# power.net
KiCad netlist of a schematic drawn in Altium Designer
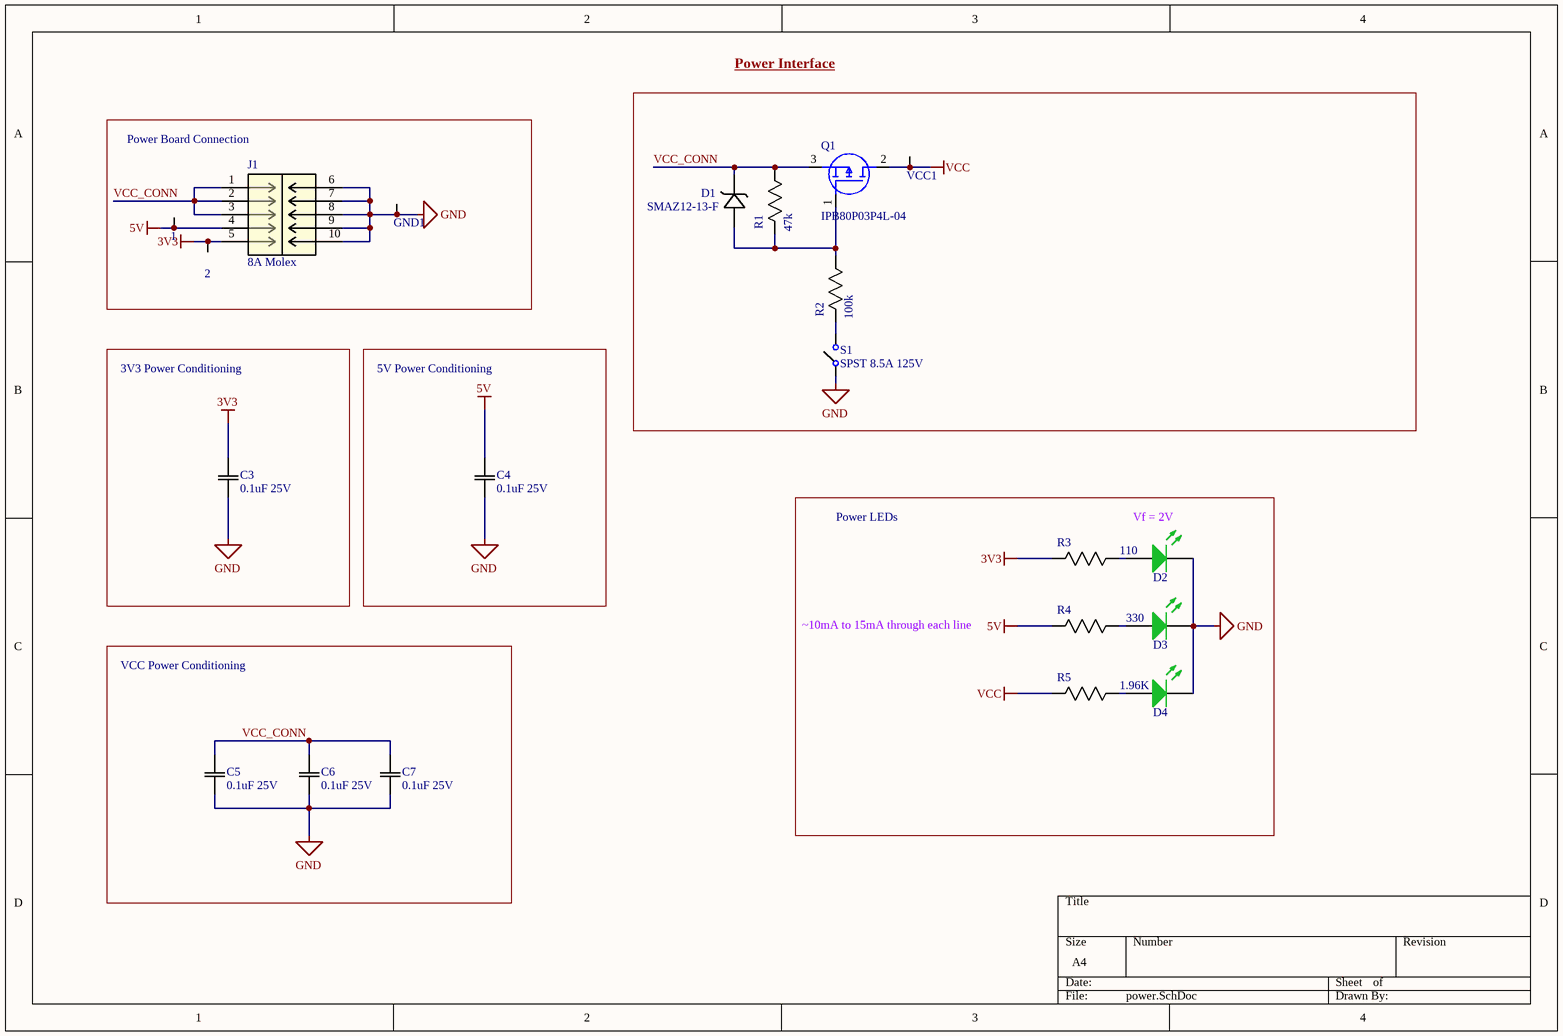
[diagram p0: power.SchDoc]

(export (version "E")
  (design (tool "Eeschema 10.0.6"))
  (components
    (comp (ref "1")
      (value "Test Point (Via)")
      (footprint "TP")
      (libsource (lib "AltiumLibraries") (part "Test Point (Via)"))
    )
    (comp (ref "2")
      (value "Test Point (Via)")
      (footprint "TP")
      (libsource (lib "AltiumLibraries") (part "Test Point (Via)"))
    )
    (comp (ref "C3")
      (value "0.1uF 25V")
      (footprint "0805")
      (description "CAP CER 0.1UF 25V X7R 0805/0603")
      (fields (field (name "TOLERANCE") "10%"))
      (libsource (lib "AltiumLibraries") (part "CAP 0.1uF 25V"))
    )
    (comp (ref "C4")
      (value "0.1uF 25V")
      (footprint "0805")
      (description "CAP CER 0.1UF 25V X7R 0805/0603")
      (fields (field (name "TOLERANCE") "10%"))
      (libsource (lib "AltiumLibraries") (part "CAP 0.1uF 25V"))
    )
    (comp (ref "C5")
      (value "0.1uF 25V")
      (footprint "0805")
      (description "CAP CER 0.1UF 25V X7R 0805/0603")
      (fields (field (name "TOLERANCE") "10%"))
      (libsource (lib "AltiumLibraries") (part "CAP 0.1uF 25V"))
    )
    (comp (ref "C6")
      (value "0.1uF 25V")
      (footprint "0805")
      (description "CAP CER 0.1UF 25V X7R 0805/0603")
      (fields (field (name "TOLERANCE") "10%"))
      (libsource (lib "AltiumLibraries") (part "CAP 0.1uF 25V"))
    )
    (comp (ref "C7")
      (value "0.1uF 25V")
      (footprint "0805")
      (description "CAP CER 0.1UF 25V X7R 0805/0603")
      (fields (field (name "TOLERANCE") "10%"))
      (libsource (lib "AltiumLibraries") (part "CAP 0.1uF 25V"))
    )
    (comp (ref "D1")
      (value "SMAZ12-13-F")
      (footprint "SMA_DIO-L")
      (description "Zener Diode 12 V 1 W ±5% Surface Mount SMA")
      (fields (field (name "COPYRIGHT") "Copyright (C) 2021 Ultra Librarian. All rights reserved."))
      (libsource (lib "AltiumLibraries") (part "DIODE ZENER 12V 1W"))
    )
    (comp (ref "D2")
      (value "LED2")
      (footprint "3.2X1.6X1.1")
      (description "Typical RED, GREEN, YELLOW, AMBER GaAs LED")
      (libsource (lib "AltiumLibraries") (part "LED GREEN SMD"))
    )
    (comp (ref "D3")
      (value "LED2")
      (footprint "3.2X1.6X1.1")
      (description "Typical RED, GREEN, YELLOW, AMBER GaAs LED")
      (libsource (lib "AltiumLibraries") (part "LED GREEN SMD"))
    )
    (comp (ref "D4")
      (value "LED2")
      (footprint "3.2X1.6X1.1")
      (description "Typical RED, GREEN, YELLOW, AMBER GaAs LED")
      (libsource (lib "AltiumLibraries") (part "LED GREEN SMD"))
    )
    (comp (ref "GND1")
      (value "Test Point (Via)")
      (footprint "TP")
      (libsource (lib "AltiumLibraries") (part "Test Point (Via)"))
    )
    (comp (ref "J1")
      (value "8A Molex")
      (footprint "MOLEX_0430451012")
      (description "CONN HEADER VERT 10POS 3MM")
      (fields (field (name "MANUFACTURER") "Molex") (field (name "MANUFACTURER PART NUMBER") "0430451012"))
      (libsource (lib "AltiumLibraries") (part "CN HDR 10POS MOLEX 0430451012"))
    )
    (comp (ref "Q1")
      (value "IPB80P03P4L-04")
      (footprint "IPB80P03P4L04")
      (description "P-Channel 30 V 80A (Tc) 137W (Tc) Surface Mount PG-TO263-3-2")
      (fields (field (name "MOUSER PART NUMBER") "726-IPB80P03P4L-04"))
      (libsource (lib "AltiumLibraries") (part "MOSFET IPB80P03P4L-04"))
    )
    (comp (ref "R1")
      (value "47k")
      (footprint "0603")
      (description "RES SMD 47k OHM 5% 1/8W 0805")
      (fields (field (name "TOLERANCE") "5%"))
      (libsource (lib "AltiumLibraries") (part "RES 47k 1/8W - 5%"))
    )
    (comp (ref "R2")
      (value "100k")
      (footprint "0603")
      (description "RES SMD 100K OHM 5% 1/8W 0805/0603")
      (fields (field (name "TOLERANCE") "5%"))
      (libsource (lib "AltiumLibraries") (part "RES 100k 1/8W - 5%"))
    )
    (comp (ref "R3")
      (value "110")
      (footprint "0603")
      (description "RES SMD 110 OHM 1% 1/8W 0805/0603")
      (fields (field (name "TOLERANCE") "1%"))
      (libsource (lib "AltiumLibraries") (part "RES 110.0 1/8W - 1%"))
    )
    (comp (ref "R4")
      (value "330")
      (footprint "0603")
      (description "RES SMD 330 OHM 5% 1/8W 0805")
      (fields (field (name "TOLERANCE") "5%"))
      (libsource (lib "AltiumLibraries") (part "RES 330.0 1/8W - 5%"))
    )
    (comp (ref "R5")
      (value "1.96K")
      (footprint "0603")
      (description "RES SMD 1.96K OHM 1% 1/8W 0805")
      (fields (field (name "TOLERANCE") "1%"))
      (libsource (lib "AltiumLibraries") (part "RES 1.96k 1/8W"))
    )
    (comp (ref "S1")
      (value "SPST 8.5A 125V")
      (footprint "SPST GF-123-0054")
      (description "SWITCH SLIDE SPST 8.5A 125V")
      (fields (field (name "MP") "GF-123-0054") (field (name "MF") "CW Industries"))
      (libsource (lib "AltiumLibraries") (part "SW SLIDE"))
    )
    (comp (ref "VCC1")
      (value "Test Point (Via)")
      (footprint "TP")
      (libsource (lib "AltiumLibraries") (part "Test Point (Via)"))
    )
  )
  (nets
    (net (code "1") (name "/VCC_CONN") (class "Default")
      (node (ref "C5") (pin "1") (pinfunction "C1_1") (pintype "passive"))
      (node (ref "C6") (pin "1") (pinfunction "C1_1") (pintype "passive"))
      (node (ref "C7") (pin "1") (pinfunction "C1_1") (pintype "passive"))
      (node (ref "D1") (pin "1") (pinfunction "1_1") (pintype "passive"))
      (node (ref "J1") (pin "1") (pinfunction "1_1") (pintype "passive"))
      (node (ref "J1") (pin "2") (pinfunction "2_2") (pintype "passive"))
      (node (ref "J1") (pin "3") (pinfunction "3_3") (pintype "passive"))
      (node (ref "Q1") (pin "3") (pinfunction "S_3") (pintype "passive"))
      (node (ref "R1") (pin "1") (pinfunction "R1_1") (pintype "passive"))
    )
    (net (code "2") (name "3V3") (class "Default")
      (node (ref "2") (pin "1") (pinfunction "1_1") (pintype "passive"))
      (node (ref "C3") (pin "1") (pinfunction "C1_1") (pintype "passive"))
      (node (ref "J1") (pin "5") (pinfunction "5_5") (pintype "passive"))
      (node (ref "R3") (pin "2") (pinfunction "R2_2") (pintype "passive"))
    )
    (net (code "3") (name "5V") (class "Default")
      (node (ref "1") (pin "1") (pinfunction "1_1") (pintype "passive"))
      (node (ref "C4") (pin "1") (pinfunction "C1_1") (pintype "passive"))
      (node (ref "J1") (pin "4") (pinfunction "4_4") (pintype "passive"))
      (node (ref "R4") (pin "2") (pinfunction "R2_2") (pintype "passive"))
    )
    (net (code "4") (name "GND") (class "Default")
      (node (ref "C3") (pin "2") (pinfunction "C2_2") (pintype "passive"))
      (node (ref "C4") (pin "2") (pinfunction "C2_2") (pintype "passive"))
      (node (ref "C5") (pin "2") (pinfunction "C2_2") (pintype "passive"))
      (node (ref "C6") (pin "2") (pinfunction "C2_2") (pintype "passive"))
      (node (ref "C7") (pin "2") (pinfunction "C2_2") (pintype "passive"))
      (node (ref "D2") (pin "2") (pinfunction "K_2") (pintype "passive"))
      (node (ref "D3") (pin "2") (pinfunction "K_2") (pintype "passive"))
      (node (ref "D4") (pin "2") (pinfunction "K_2") (pintype "passive"))
      (node (ref "GND1") (pin "1") (pinfunction "1_1") (pintype "passive"))
      (node (ref "J1") (pin "10") (pinfunction "10_10") (pintype "passive"))
      (node (ref "J1") (pin "6") (pinfunction "6_6") (pintype "passive"))
      (node (ref "J1") (pin "7") (pinfunction "7_7") (pintype "passive"))
      (node (ref "J1") (pin "8") (pinfunction "8_8") (pintype "passive"))
      (node (ref "J1") (pin "9") (pinfunction "9_9") (pintype "passive"))
      (node (ref "S1") (pin "0") (pinfunction "0_0") (pintype "passive"))
    )
    (net (code "5") (name "Net-(D2-A)") (class "Default")
      (node (ref "D2") (pin "1") (pinfunction "A_1") (pintype "passive"))
      (node (ref "R3") (pin "1") (pinfunction "R1_1") (pintype "passive"))
    )
    (net (code "6") (name "Net-(D3-A)") (class "Default")
      (node (ref "D3") (pin "1") (pinfunction "A_1") (pintype "passive"))
      (node (ref "R4") (pin "1") (pinfunction "R1_1") (pintype "passive"))
    )
    (net (code "7") (name "Net-(D4-A)") (class "Default")
      (node (ref "D4") (pin "1") (pinfunction "A_1") (pintype "passive"))
      (node (ref "R5") (pin "1") (pinfunction "R1_1") (pintype "passive"))
    )
    (net (code "8") (name "Net-(Q1-G)") (class "Default")
      (node (ref "D1") (pin "2") (pinfunction "2_2") (pintype "passive"))
      (node (ref "Q1") (pin "1") (pinfunction "G_1") (pintype "passive"))
      (node (ref "R1") (pin "2") (pinfunction "R2_2") (pintype "passive"))
      (node (ref "R2") (pin "1") (pinfunction "R1_1") (pintype "passive"))
    )
    (net (code "9") (name "Net-(R2-R2)") (class "Default")
      (node (ref "R2") (pin "2") (pinfunction "R2_2") (pintype "passive"))
      (node (ref "S1") (pin "1") (pinfunction "1_1") (pintype "passive"))
    )
    (net (code "10") (name "VCC") (class "Default")
      (node (ref "Q1") (pin "2") (pinfunction "D_2") (pintype "passive"))
      (node (ref "R5") (pin "2") (pinfunction "R2_2") (pintype "passive"))
      (node (ref "VCC1") (pin "1") (pinfunction "1_1") (pintype "passive"))
    )
  )
)
